# SCH_TerrariumMonitor_2025-09-21.net
KiCad netlist of a schematic drawn in EasyEDA
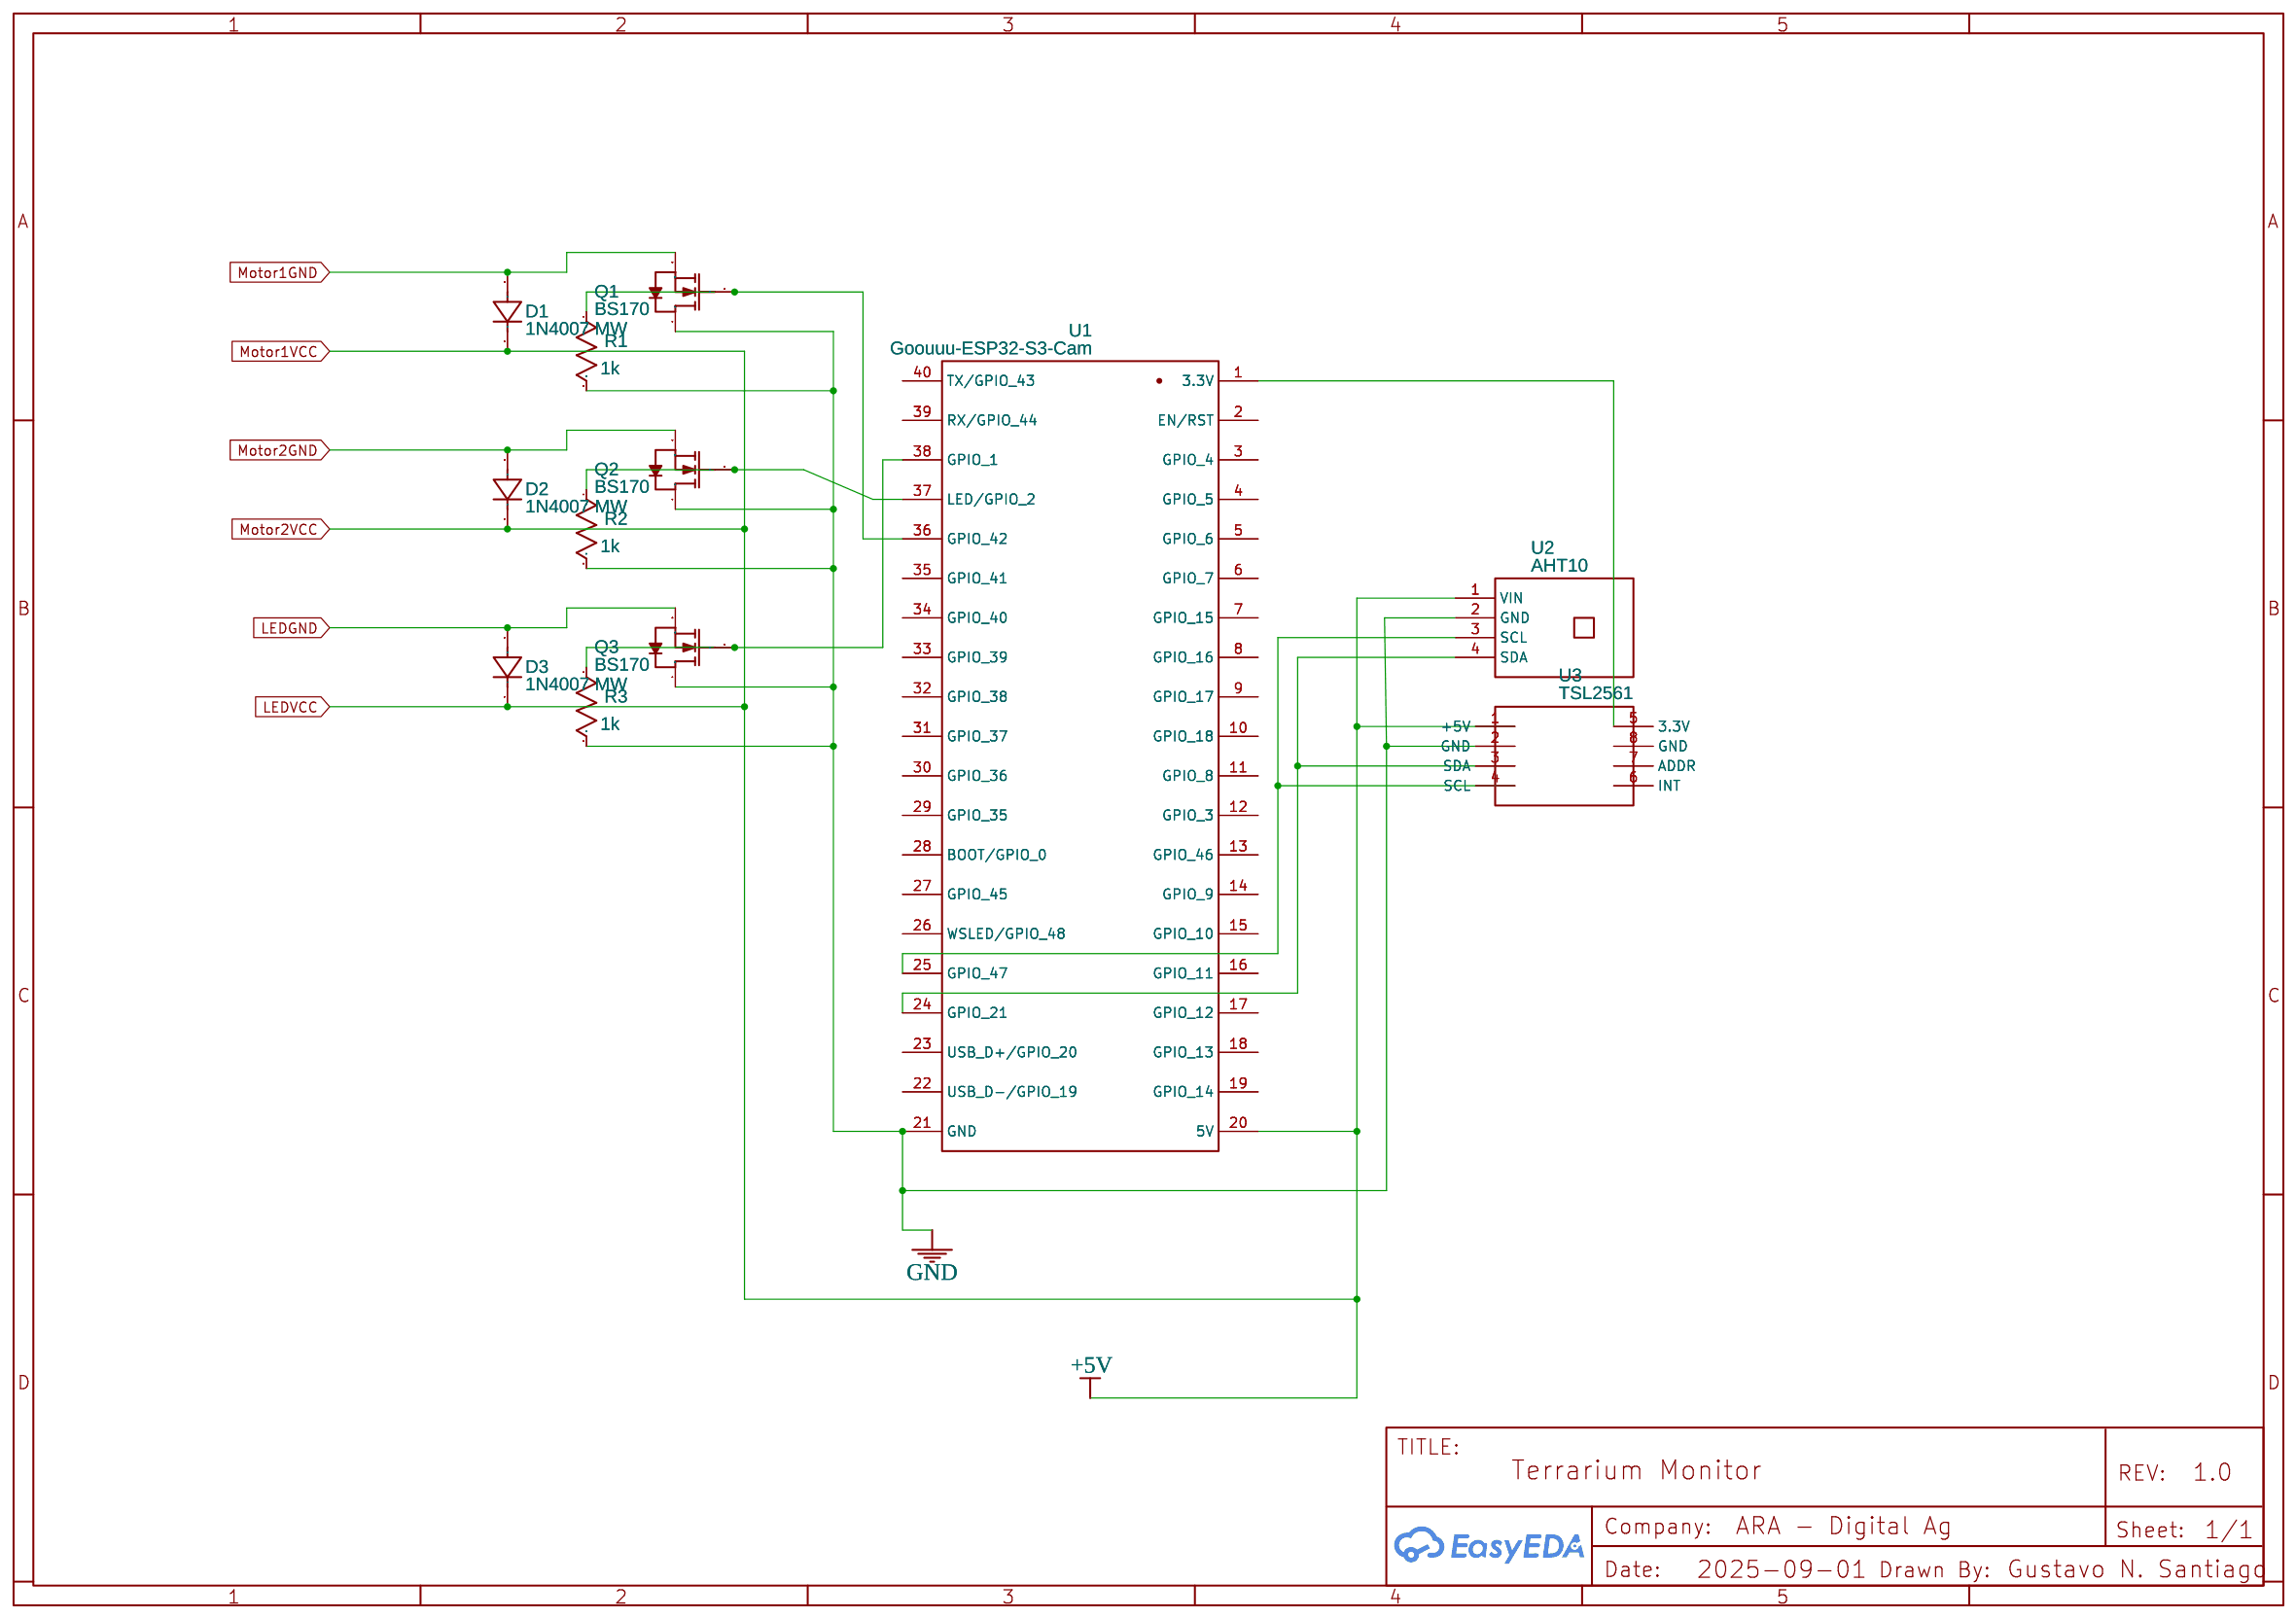
[diagram p0: schematic sheet]

(export (version "E")
  (design (tool "Eeschema 10.0.6"))
  (components
    (comp (ref "D1")
      (value "1N4007 MW")
      (fields (field (name "Manufacturer") "YFW(佑风微)"))
      (libsource (lib "") (part "1N4007 MW"))
    )
    (comp (ref "D2")
      (value "1N4007 MW")
      (fields (field (name "Manufacturer") "YFW(佑风微)"))
      (libsource (lib "") (part "1N4007 MW"))
    )
    (comp (ref "D3")
      (value "1N4007 MW")
      (fields (field (name "Manufacturer") "YFW(佑风微)"))
      (libsource (lib "") (part "1N4007 MW"))
    )
    (comp (ref "Q1")
      (value "BS170")
      (fields (field (name "Manufacturer") "onsemi(安森美)"))
      (libsource (lib "") (part "BS170"))
    )
    (comp (ref "Q2")
      (value "BS170")
      (fields (field (name "Manufacturer") "onsemi(安森美)"))
      (libsource (lib "") (part "BS170"))
    )
    (comp (ref "Q3")
      (value "BS170")
      (fields (field (name "Manufacturer") "onsemi(安森美)"))
      (libsource (lib "") (part "BS170"))
    )
    (comp (ref "R1") (value "1k") (libsource (lib "") (part "R_0603_US")))
    (comp (ref "R2") (value "1k") (libsource (lib "") (part "R_0603_US")))
    (comp (ref "R3") (value "1k") (libsource (lib "") (part "R_0603_US")))
    (comp (ref "U1")
      (value "Goouuu-ESP32-S3-Cam")
      (fields
        (field (name "Manufacturer Part") "FreenoveESP-S3 WROOM")
        (field (name "Manufacturer") "Freenove")
      )
      (libsource (lib "") (part "Goouuu-ESP32-S3-Cam"))
    )
    (comp (ref "U2") (value "AHT10") (libsource (lib "") (part "AHT10")))
    (comp (ref "U3") (value "TSL2561") (libsource (lib "") (part "TSL2561")))
  )
  (nets
    (net (code "1") (name "GND") (class "Default")
      (node (ref "Q1") (pin "1") (pinfunction "D_1") (pintype "unspecified"))
      (node (ref "Q2") (pin "1") (pinfunction "D_1") (pintype "unspecified"))
      (node (ref "Q3") (pin "1") (pinfunction "D_1") (pintype "unspecified"))
      (node (ref "R1") (pin "2") (pinfunction "2_2") (pintype "unspecified"))
      (node (ref "R2") (pin "2") (pinfunction "2_2") (pintype "unspecified"))
      (node (ref "R3") (pin "2") (pinfunction "2_2") (pintype "unspecified"))
      (node (ref "U1") (pin "21") (pinfunction "GND_21") (pintype "unspecified"))
      (node (ref "U2") (pin "2") (pinfunction "GND_2") (pintype "unspecified"))
      (node (ref "U3") (pin "2") (pinfunction "GND_2") (pintype "unspecified"))
    )
    (net (code "2") (name "LEDGND") (class "Default")
      (node (ref "D3") (pin "2") (pinfunction "A_2") (pintype "unspecified"))
      (node (ref "Q3") (pin "3") (pinfunction "S_3") (pintype "unspecified"))
    )
    (net (code "3") (name "LEDVCC") (class "Default")
      (node (ref "D1") (pin "1") (pinfunction "K_1") (pintype "unspecified"))
      (node (ref "D2") (pin "1") (pinfunction "K_1") (pintype "unspecified"))
      (node (ref "D3") (pin "1") (pinfunction "K_1") (pintype "unspecified"))
      (node (ref "U1") (pin "20") (pinfunction "5V_20") (pintype "unspecified"))
      (node (ref "U2") (pin "1") (pinfunction "VIN_1") (pintype "unspecified"))
      (node (ref "U3") (pin "1") (pinfunction "+5V_1") (pintype "unspecified"))
    )
    (net (code "4") (name "Motor1GND") (class "Default")
      (node (ref "D1") (pin "2") (pinfunction "A_2") (pintype "unspecified"))
      (node (ref "Q1") (pin "3") (pinfunction "S_3") (pintype "unspecified"))
    )
    (net (code "5") (name "Motor2GND") (class "Default")
      (node (ref "D2") (pin "2") (pinfunction "A_2") (pintype "unspecified"))
      (node (ref "Q2") (pin "3") (pinfunction "S_3") (pintype "unspecified"))
    )
    (net (code "6") (name "Net-(Q1-G)") (class "Default")
      (node (ref "Q1") (pin "2") (pinfunction "G_2") (pintype "unspecified"))
      (node (ref "R1") (pin "1") (pinfunction "1_1") (pintype "unspecified"))
      (node (ref "U1") (pin "36") (pinfunction "GPIO_42_36") (pintype "unspecified"))
    )
    (net (code "7") (name "Net-(Q2-G)") (class "Default")
      (node (ref "Q2") (pin "2") (pinfunction "G_2") (pintype "unspecified"))
      (node (ref "R2") (pin "1") (pinfunction "1_1") (pintype "unspecified"))
      (node (ref "U1") (pin "37") (pinfunction "LED/GPIO_2_37") (pintype "unspecified"))
    )
    (net (code "8") (name "Net-(Q3-G)") (class "Default")
      (node (ref "Q3") (pin "2") (pinfunction "G_2") (pintype "unspecified"))
      (node (ref "R3") (pin "1") (pinfunction "1_1") (pintype "unspecified"))
      (node (ref "U1") (pin "38") (pinfunction "GPIO_1_38") (pintype "unspecified"))
    )
    (net (code "9") (name "Net-(U1-3.3V)") (class "Default")
      (node (ref "U1") (pin "1") (pinfunction "3.3V_1") (pintype "unspecified"))
      (node (ref "U3") (pin "5") (pinfunction "3.3V_5") (pintype "unspecified"))
    )
    (net (code "10") (name "Net-(U1-GPIO_21)") (class "Default")
      (node (ref "U1") (pin "24") (pinfunction "GPIO_21_24") (pintype "unspecified"))
      (node (ref "U2") (pin "4") (pinfunction "SDA_4") (pintype "unspecified"))
      (node (ref "U3") (pin "3") (pinfunction "SDA_3") (pintype "unspecified"))
    )
    (net (code "11") (name "Net-(U1-GPIO_47)") (class "Default")
      (node (ref "U1") (pin "25") (pinfunction "GPIO_47_25") (pintype "passive"))
      (node (ref "U2") (pin "3") (pinfunction "SCL_3") (pintype "unspecified"))
      (node (ref "U3") (pin "4") (pinfunction "SCL_4") (pintype "unspecified"))
    )
    (net (code "12") (name "unconnected-(U1-BOOT{slash}GPIO_0-Pad28)") (class "Default")
      (node (ref "U1") (pin "28") (pinfunction "BOOT/GPIO_0_28") (pintype "unspecified"))
    )
    (net (code "13") (name "unconnected-(U1-EN{slash}RST-Pad2)") (class "Default")
      (node (ref "U1") (pin "2") (pinfunction "EN/RST_2") (pintype "passive"))
    )
    (net (code "14") (name "unconnected-(U1-GPIO_3-Pad12)") (class "Default")
      (node (ref "U1") (pin "12") (pinfunction "GPIO_3_12") (pintype "unspecified"))
    )
    (net (code "15") (name "unconnected-(U1-GPIO_4-Pad3)") (class "Default")
      (node (ref "U1") (pin "3") (pinfunction "GPIO_4_3") (pintype "unspecified"))
    )
    (net (code "16") (name "unconnected-(U1-GPIO_5-Pad4)") (class "Default")
      (node (ref "U1") (pin "4") (pinfunction "GPIO_5_4") (pintype "unspecified"))
    )
    (net (code "17") (name "unconnected-(U1-GPIO_6-Pad5)") (class "Default")
      (node (ref "U1") (pin "5") (pinfunction "GPIO_6_5") (pintype "unspecified"))
    )
    (net (code "18") (name "unconnected-(U1-GPIO_7-Pad6)") (class "Default")
      (node (ref "U1") (pin "6") (pinfunction "GPIO_7_6") (pintype "unspecified"))
    )
    (net (code "19") (name "unconnected-(U1-GPIO_8-Pad11)") (class "Default")
      (node (ref "U1") (pin "11") (pinfunction "GPIO_8_11") (pintype "unspecified"))
    )
    (net (code "20") (name "unconnected-(U1-GPIO_9-Pad14)") (class "Default")
      (node (ref "U1") (pin "14") (pinfunction "GPIO_9_14") (pintype "passive"))
    )
    (net (code "21") (name "unconnected-(U1-GPIO_10-Pad15)") (class "Default")
      (node (ref "U1") (pin "15") (pinfunction "GPIO_10_15") (pintype "passive"))
    )
    (net (code "22") (name "unconnected-(U1-GPIO_11-Pad16)") (class "Default")
      (node (ref "U1") (pin "16") (pinfunction "GPIO_11_16") (pintype "passive"))
    )
    (net (code "23") (name "unconnected-(U1-GPIO_12-Pad17)") (class "Default")
      (node (ref "U1") (pin "17") (pinfunction "GPIO_12_17") (pintype "passive"))
    )
    (net (code "24") (name "unconnected-(U1-GPIO_13-Pad18)") (class "Default")
      (node (ref "U1") (pin "18") (pinfunction "GPIO_13_18") (pintype "unspecified"))
    )
    (net (code "25") (name "unconnected-(U1-GPIO_14-Pad19)") (class "Default")
      (node (ref "U1") (pin "19") (pinfunction "GPIO_14_19") (pintype "unspecified"))
    )
    (net (code "26") (name "unconnected-(U1-GPIO_15-Pad7)") (class "Default")
      (node (ref "U1") (pin "7") (pinfunction "GPIO_15_7") (pintype "unspecified"))
    )
    (net (code "27") (name "unconnected-(U1-GPIO_16-Pad8)") (class "Default")
      (node (ref "U1") (pin "8") (pinfunction "GPIO_16_8") (pintype "unspecified"))
    )
    (net (code "28") (name "unconnected-(U1-GPIO_17-Pad9)") (class "Default")
      (node (ref "U1") (pin "9") (pinfunction "GPIO_17_9") (pintype "unspecified"))
    )
    (net (code "29") (name "unconnected-(U1-GPIO_18-Pad10)") (class "Default")
      (node (ref "U1") (pin "10") (pinfunction "GPIO_18_10") (pintype "unspecified"))
    )
    (net (code "30") (name "unconnected-(U1-GPIO_35-Pad29)") (class "Default")
      (node (ref "U1") (pin "29") (pinfunction "GPIO_35_29") (pintype "unspecified"))
    )
    (net (code "31") (name "unconnected-(U1-GPIO_36-Pad30)") (class "Default")
      (node (ref "U1") (pin "30") (pinfunction "GPIO_36_30") (pintype "unspecified"))
    )
    (net (code "32") (name "unconnected-(U1-GPIO_37-Pad31)") (class "Default")
      (node (ref "U1") (pin "31") (pinfunction "GPIO_37_31") (pintype "unspecified"))
    )
    (net (code "33") (name "unconnected-(U1-GPIO_38-Pad32)") (class "Default")
      (node (ref "U1") (pin "32") (pinfunction "GPIO_38_32") (pintype "unspecified"))
    )
    (net (code "34") (name "unconnected-(U1-GPIO_39-Pad33)") (class "Default")
      (node (ref "U1") (pin "33") (pinfunction "GPIO_39_33") (pintype "unspecified"))
    )
    (net (code "35") (name "unconnected-(U1-GPIO_40-Pad34)") (class "Default")
      (node (ref "U1") (pin "34") (pinfunction "GPIO_40_34") (pintype "unspecified"))
    )
    (net (code "36") (name "unconnected-(U1-GPIO_41-Pad35)") (class "Default")
      (node (ref "U1") (pin "35") (pinfunction "GPIO_41_35") (pintype "unspecified"))
    )
    (net (code "37") (name "unconnected-(U1-GPIO_45-Pad27)") (class "Default")
      (node (ref "U1") (pin "27") (pinfunction "GPIO_45_27") (pintype "unspecified"))
    )
    (net (code "38") (name "unconnected-(U1-GPIO_46-Pad13)") (class "Default")
      (node (ref "U1") (pin "13") (pinfunction "GPIO_46_13") (pintype "unspecified"))
    )
    (net (code "39") (name "unconnected-(U1-RX{slash}GPIO_44-Pad39)") (class "Default")
      (node (ref "U1") (pin "39") (pinfunction "RX/GPIO_44_39") (pintype "unspecified"))
    )
    (net (code "40") (name "unconnected-(U1-TX{slash}GPIO_43-Pad40)") (class "Default")
      (node (ref "U1") (pin "40") (pinfunction "TX/GPIO_43_40") (pintype "unspecified"))
    )
    (net (code "41") (name "unconnected-(U1-USB_D+{slash}GPIO_20-Pad23)") (class "Default")
      (node (ref "U1") (pin "23") (pinfunction "USB_D+/GPIO_20_23") (pintype "unspecified"))
    )
    (net (code "42") (name "unconnected-(U1-USB_D-{slash}GPIO_19-Pad22)") (class "Default")
      (node (ref "U1") (pin "22") (pinfunction "USB_D-/GPIO_19_22") (pintype "unspecified"))
    )
    (net (code "43") (name "unconnected-(U1-WSLED{slash}GPIO_48-Pad26)") (class "Default")
      (node (ref "U1") (pin "26") (pinfunction "WSLED/GPIO_48_26") (pintype "unspecified"))
    )
    (net (code "44") (name "unconnected-(U3-ADDR-Pad7)") (class "Default")
      (node (ref "U3") (pin "7") (pinfunction "ADDR_7") (pintype "unspecified"))
    )
    (net (code "45") (name "unconnected-(U3-GND-Pad8)") (class "Default")
      (node (ref "U3") (pin "8") (pinfunction "GND_8") (pintype "unspecified"))
    )
    (net (code "46") (name "unconnected-(U3-INT-Pad6)") (class "Default")
      (node (ref "U3") (pin "6") (pinfunction "INT_6") (pintype "unspecified"))
    )
  )
)
